# led_quadcoopter.net
KiCad netlist of a schematic drawn in EAGLE
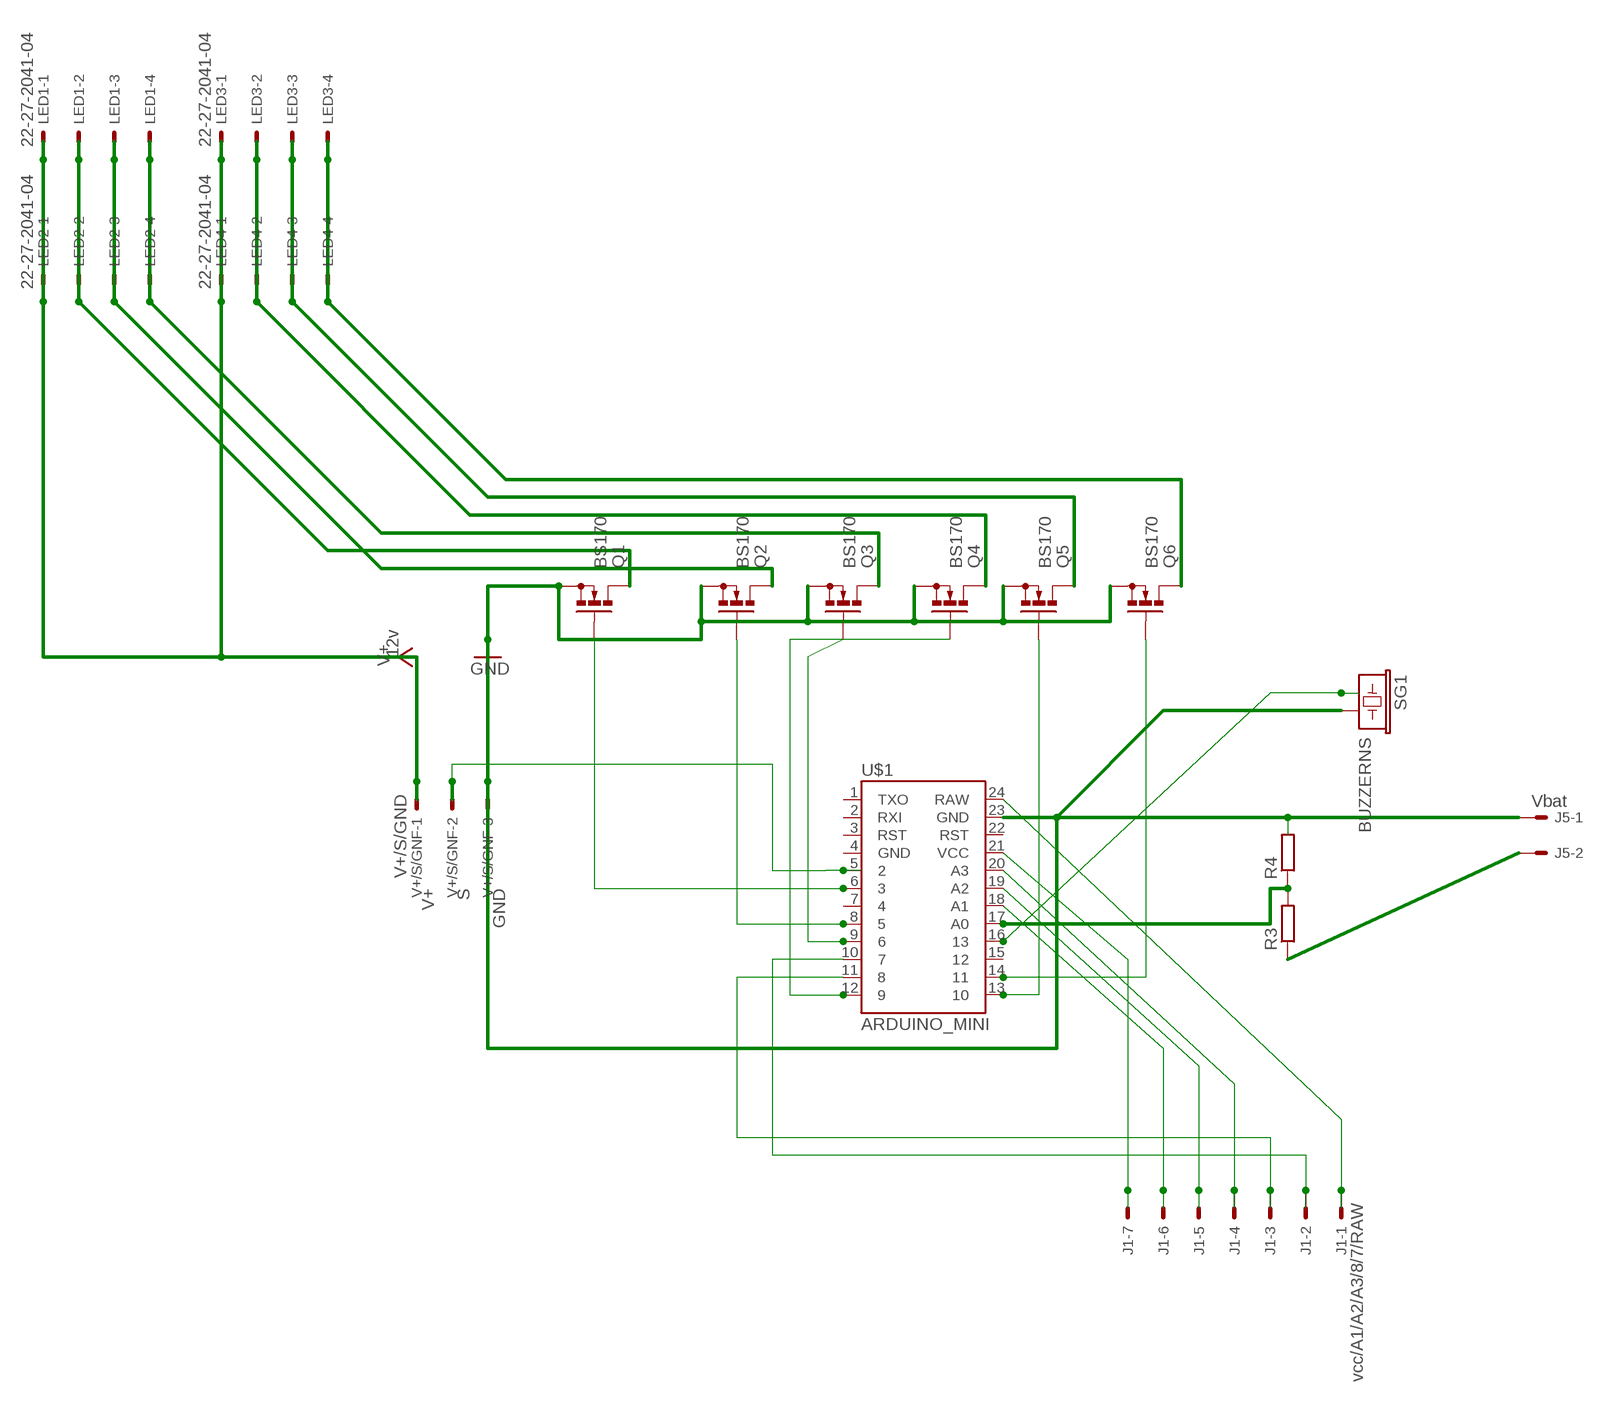
[diagram p0: schematic, sheet 1]

(export (version "E")
  (design (tool "Eeschema 10.0.6"))
  (components
    (comp (ref "J1")
      (value "vcc/A1/A2/A3/8/7/RAW")
      (footprint "eagle-import:6410-07")
      (libsource (lib "eagle-import") (part "22-?-0727-2071"))
    )
    (comp (ref "J5")
      (value "Vbat")
      (footprint "eagle-import:6410-02")
      (libsource (lib "eagle-import") (part "22-?-0227-2021"))
    )
    (comp (ref "LED1")
      (value "22-27-2041-04")
      (footprint "eagle-import:6410-04")
      (libsource (lib "eagle-import") (part "22-?-0427-2041"))
    )
    (comp (ref "LED2")
      (value "22-27-2041-04")
      (footprint "eagle-import:6410-04")
      (libsource (lib "eagle-import") (part "22-?-0427-2041"))
    )
    (comp (ref "LED3")
      (value "22-27-2041-04")
      (footprint "eagle-import:6410-04")
      (libsource (lib "eagle-import") (part "22-?-0427-2041"))
    )
    (comp (ref "LED4")
      (value "22-27-2041-04")
      (footprint "eagle-import:6410-04")
      (libsource (lib "eagle-import") (part "22-?-0427-2041"))
    )
    (comp (ref "Q1")
      (value "BS170")
      (footprint "eagle-import:SOT54E")
      (libsource (lib "eagle-import") (part "BS170"))
    )
    (comp (ref "Q2")
      (value "BS170")
      (footprint "eagle-import:SOT54E")
      (libsource (lib "eagle-import") (part "BS170"))
    )
    (comp (ref "Q3")
      (value "BS170")
      (footprint "eagle-import:SOT54E")
      (libsource (lib "eagle-import") (part "BS170"))
    )
    (comp (ref "Q4")
      (value "BS170")
      (footprint "eagle-import:SOT54E")
      (libsource (lib "eagle-import") (part "BS170"))
    )
    (comp (ref "Q5")
      (value "BS170")
      (footprint "eagle-import:SOT54E")
      (libsource (lib "eagle-import") (part "BS170"))
    )
    (comp (ref "Q6")
      (value "BS170")
      (footprint "eagle-import:SOT54E")
      (libsource (lib "eagle-import") (part "BS170"))
    )
    (comp (ref "R3")
      (value "R-EU_0207/10")
      (footprint "eagle-import:0207_10")
      (libsource (lib "eagle-import") (part "R-EU_0207/10"))
    )
    (comp (ref "R4")
      (value "R-EU_0207/10")
      (footprint "eagle-import:0207_10")
      (libsource (lib "eagle-import") (part "R-EU_0207/10"))
    )
    (comp (ref "SG1")
      (value "BUZZERNS")
      (footprint "eagle-import:BUZZER-12MM-NS")
      (libsource (lib "eagle-import") (part "BUZZERNS"))
    )
    (comp (ref "U$1")
      (value "ARDUINO_MINI")
      (footprint "eagle-import:ARDUINO_MINI")
      (libsource (lib "eagle-import") (part "ARDUINO_MINI"))
    )
    (comp (ref "V+/S/GNF")
      (value "V+/S/GND")
      (footprint "eagle-import:6410-03")
      (fields
        (field (name "MF") "V+")
        (field (name "OC_FARNELL") "GND")
        (field (name "OC_NEWARK") "S")
        (field (name "OC_FARNELL_1") "GND")
        (field (name "OC_NEWARK_1") "S")
      )
      (libsource (lib "eagle-import") (part "22-?-0327-2031"))
    )
  )
  (nets
    (net (code "1") (name "GND") (class "Default")
      (node (ref "J5") (pin "1") (pinfunction "S_1") (pintype "passive"))
      (node (ref "Q1") (pin "S") (pinfunction "S_S") (pintype "passive"))
      (node (ref "Q2") (pin "S") (pinfunction "S_S") (pintype "passive"))
      (node (ref "Q3") (pin "S") (pinfunction "S_S") (pintype "passive"))
      (node (ref "Q4") (pin "S") (pinfunction "S_S") (pintype "passive"))
      (node (ref "Q5") (pin "S") (pinfunction "S_S") (pintype "passive"))
      (node (ref "Q6") (pin "S") (pinfunction "S_S") (pintype "passive"))
      (node (ref "R4") (pin "2") (pinfunction "2_2") (pintype "passive"))
      (node (ref "SG1") (pin "-") (pinfunction "2_-") (pintype "passive"))
      (node (ref "U$1") (pin "23") (pinfunction "GND_23") (pintype "bidirectional"))
      (node (ref "V+/S/GNF") (pin "3") (pinfunction "S_3") (pintype "passive"))
    )
    (net (code "2") (name "Net-(J1A-S)") (class "Default")
      (node (ref "J1") (pin "1") (pinfunction "S_1") (pintype "passive"))
      (node (ref "U$1") (pin "24") (pinfunction "RAW_24") (pintype "bidirectional"))
    )
    (net (code "3") (name "Net-(J1B-S)") (class "Default")
      (node (ref "J1") (pin "2") (pinfunction "S_2") (pintype "passive"))
      (node (ref "U$1") (pin "10") (pinfunction "7_10") (pintype "bidirectional"))
    )
    (net (code "4") (name "Net-(J1C-S)") (class "Default")
      (node (ref "J1") (pin "3") (pinfunction "S_3") (pintype "passive"))
      (node (ref "U$1") (pin "11") (pinfunction "8_11") (pintype "bidirectional"))
    )
    (net (code "5") (name "Net-(J1D-S)") (class "Default")
      (node (ref "J1") (pin "4") (pinfunction "S_4") (pintype "passive"))
      (node (ref "U$1") (pin "20") (pinfunction "A3_20") (pintype "bidirectional"))
    )
    (net (code "6") (name "Net-(J1E-S)") (class "Default")
      (node (ref "J1") (pin "5") (pinfunction "S_5") (pintype "passive"))
      (node (ref "U$1") (pin "19") (pinfunction "A2_19") (pintype "bidirectional"))
    )
    (net (code "7") (name "Net-(J1F-S)") (class "Default")
      (node (ref "J1") (pin "6") (pinfunction "S_6") (pintype "passive"))
      (node (ref "U$1") (pin "18") (pinfunction "A1_18") (pintype "bidirectional"))
    )
    (net (code "8") (name "Net-(J1G-S)") (class "Default")
      (node (ref "J1") (pin "7") (pinfunction "S_7") (pintype "passive"))
      (node (ref "U$1") (pin "21") (pinfunction "VCC_21") (pintype "bidirectional"))
    )
    (net (code "9") (name "Net-(J5B-S)") (class "Default")
      (node (ref "J5") (pin "2") (pinfunction "S_2") (pintype "passive"))
      (node (ref "R3") (pin "1") (pinfunction "1_1") (pintype "passive"))
    )
    (net (code "10") (name "Net-(LED1B-S)") (class "Default")
      (node (ref "LED1") (pin "2") (pinfunction "S_2") (pintype "passive"))
      (node (ref "LED2") (pin "2") (pinfunction "S_2") (pintype "passive"))
      (node (ref "Q1") (pin "D") (pinfunction "D_D") (pintype "passive"))
    )
    (net (code "11") (name "Net-(LED1C-S)") (class "Default")
      (node (ref "LED1") (pin "3") (pinfunction "S_3") (pintype "passive"))
      (node (ref "LED2") (pin "3") (pinfunction "S_3") (pintype "passive"))
      (node (ref "Q2") (pin "D") (pinfunction "D_D") (pintype "passive"))
    )
    (net (code "12") (name "Net-(LED1D-S)") (class "Default")
      (node (ref "LED1") (pin "4") (pinfunction "S_4") (pintype "passive"))
      (node (ref "LED2") (pin "4") (pinfunction "S_4") (pintype "passive"))
      (node (ref "Q3") (pin "D") (pinfunction "D_D") (pintype "passive"))
    )
    (net (code "13") (name "Net-(LED3B-S)") (class "Default")
      (node (ref "LED3") (pin "2") (pinfunction "S_2") (pintype "passive"))
      (node (ref "LED4") (pin "2") (pinfunction "S_2") (pintype "passive"))
      (node (ref "Q4") (pin "D") (pinfunction "D_D") (pintype "passive"))
    )
    (net (code "14") (name "Net-(LED3C-S)") (class "Default")
      (node (ref "LED3") (pin "3") (pinfunction "S_3") (pintype "passive"))
      (node (ref "LED4") (pin "3") (pinfunction "S_3") (pintype "passive"))
      (node (ref "Q5") (pin "D") (pinfunction "D_D") (pintype "passive"))
    )
    (net (code "15") (name "Net-(LED3D-S)") (class "Default")
      (node (ref "LED3") (pin "4") (pinfunction "S_4") (pintype "passive"))
      (node (ref "LED4") (pin "4") (pinfunction "S_4") (pintype "passive"))
      (node (ref "Q6") (pin "D") (pinfunction "D_D") (pintype "passive"))
    )
    (net (code "16") (name "Net-(SG1-1)") (class "Default")
      (node (ref "SG1") (pin "+") (pinfunction "1_+") (pintype "passive"))
      (node (ref "U$1") (pin "16") (pinfunction "13_16") (pintype "bidirectional"))
    )
    (net (code "17") (name "Net-(U$1-2)") (class "Default")
      (node (ref "U$1") (pin "5") (pinfunction "2_5") (pintype "bidirectional"))
      (node (ref "V+/S/GNF") (pin "2") (pinfunction "S_2") (pintype "passive"))
    )
    (net (code "18") (name "Net-(U$1-3)") (class "Default")
      (node (ref "Q1") (pin "G") (pinfunction "G_G") (pintype "passive"))
      (node (ref "U$1") (pin "6") (pinfunction "3_6") (pintype "bidirectional"))
    )
    (net (code "19") (name "Net-(U$1-5)") (class "Default")
      (node (ref "Q2") (pin "G") (pinfunction "G_G") (pintype "passive"))
      (node (ref "U$1") (pin "8") (pinfunction "5_8") (pintype "bidirectional"))
    )
    (net (code "20") (name "Net-(U$1-6)") (class "Default")
      (node (ref "Q3") (pin "G") (pinfunction "G_G") (pintype "passive"))
      (node (ref "U$1") (pin "9") (pinfunction "6_9") (pintype "bidirectional"))
    )
    (net (code "21") (name "Net-(U$1-9)") (class "Default")
      (node (ref "Q4") (pin "G") (pinfunction "G_G") (pintype "passive"))
      (node (ref "U$1") (pin "12") (pinfunction "9_12") (pintype "bidirectional"))
    )
    (net (code "22") (name "Net-(U$1-10)") (class "Default")
      (node (ref "Q5") (pin "G") (pinfunction "G_G") (pintype "passive"))
      (node (ref "U$1") (pin "13") (pinfunction "10_13") (pintype "bidirectional"))
    )
    (net (code "23") (name "Net-(U$1-11)") (class "Default")
      (node (ref "Q6") (pin "G") (pinfunction "G_G") (pintype "passive"))
      (node (ref "U$1") (pin "14") (pinfunction "11_14") (pintype "bidirectional"))
    )
    (net (code "24") (name "Net-(U$1-A0)") (class "Default")
      (node (ref "R3") (pin "2") (pinfunction "2_2") (pintype "passive"))
      (node (ref "R4") (pin "1") (pinfunction "1_1") (pintype "passive"))
      (node (ref "U$1") (pin "17") (pinfunction "A0_17") (pintype "bidirectional"))
    )
    (net (code "25") (name "V+") (class "Default")
      (node (ref "LED1") (pin "1") (pinfunction "S_1") (pintype "passive"))
      (node (ref "LED2") (pin "1") (pinfunction "S_1") (pintype "passive"))
      (node (ref "LED3") (pin "1") (pinfunction "S_1") (pintype "passive"))
      (node (ref "LED4") (pin "1") (pinfunction "S_1") (pintype "passive"))
      (node (ref "V+/S/GNF") (pin "1") (pinfunction "S_1") (pintype "passive"))
    )
    (net (code "26") (name "unconnected-(U$1-4-Pad7)") (class "Default")
      (node (ref "U$1") (pin "7") (pinfunction "4_7") (pintype "bidirectional"))
    )
    (net (code "27") (name "unconnected-(U$1-12-Pad15)") (class "Default")
      (node (ref "U$1") (pin "15") (pinfunction "12_15") (pintype "bidirectional"))
    )
    (net (code "28") (name "unconnected-(U$1-GND-Pad4)") (class "Default")
      (node (ref "U$1") (pin "4") (pinfunction "GND_4") (pintype "bidirectional"))
    )
    (net (code "29") (name "unconnected-(U$1-RST-Pad3)") (class "Default")
      (node (ref "U$1") (pin "3") (pinfunction "RST_3") (pintype "bidirectional"))
    )
    (net (code "30") (name "unconnected-(U$1-RST-Pad22)") (class "Default")
      (node (ref "U$1") (pin "22") (pinfunction "RST_22") (pintype "bidirectional"))
    )
    (net (code "31") (name "unconnected-(U$1-RXI-Pad2)") (class "Default")
      (node (ref "U$1") (pin "2") (pinfunction "RXI_2") (pintype "bidirectional"))
    )
    (net (code "32") (name "unconnected-(U$1-TXO-Pad1)") (class "Default")
      (node (ref "U$1") (pin "1") (pinfunction "TXO_1") (pintype "bidirectional"))
    )
  )
)
